# 407-io.net
KiCad netlist of a schematic drawn in Altium Designer
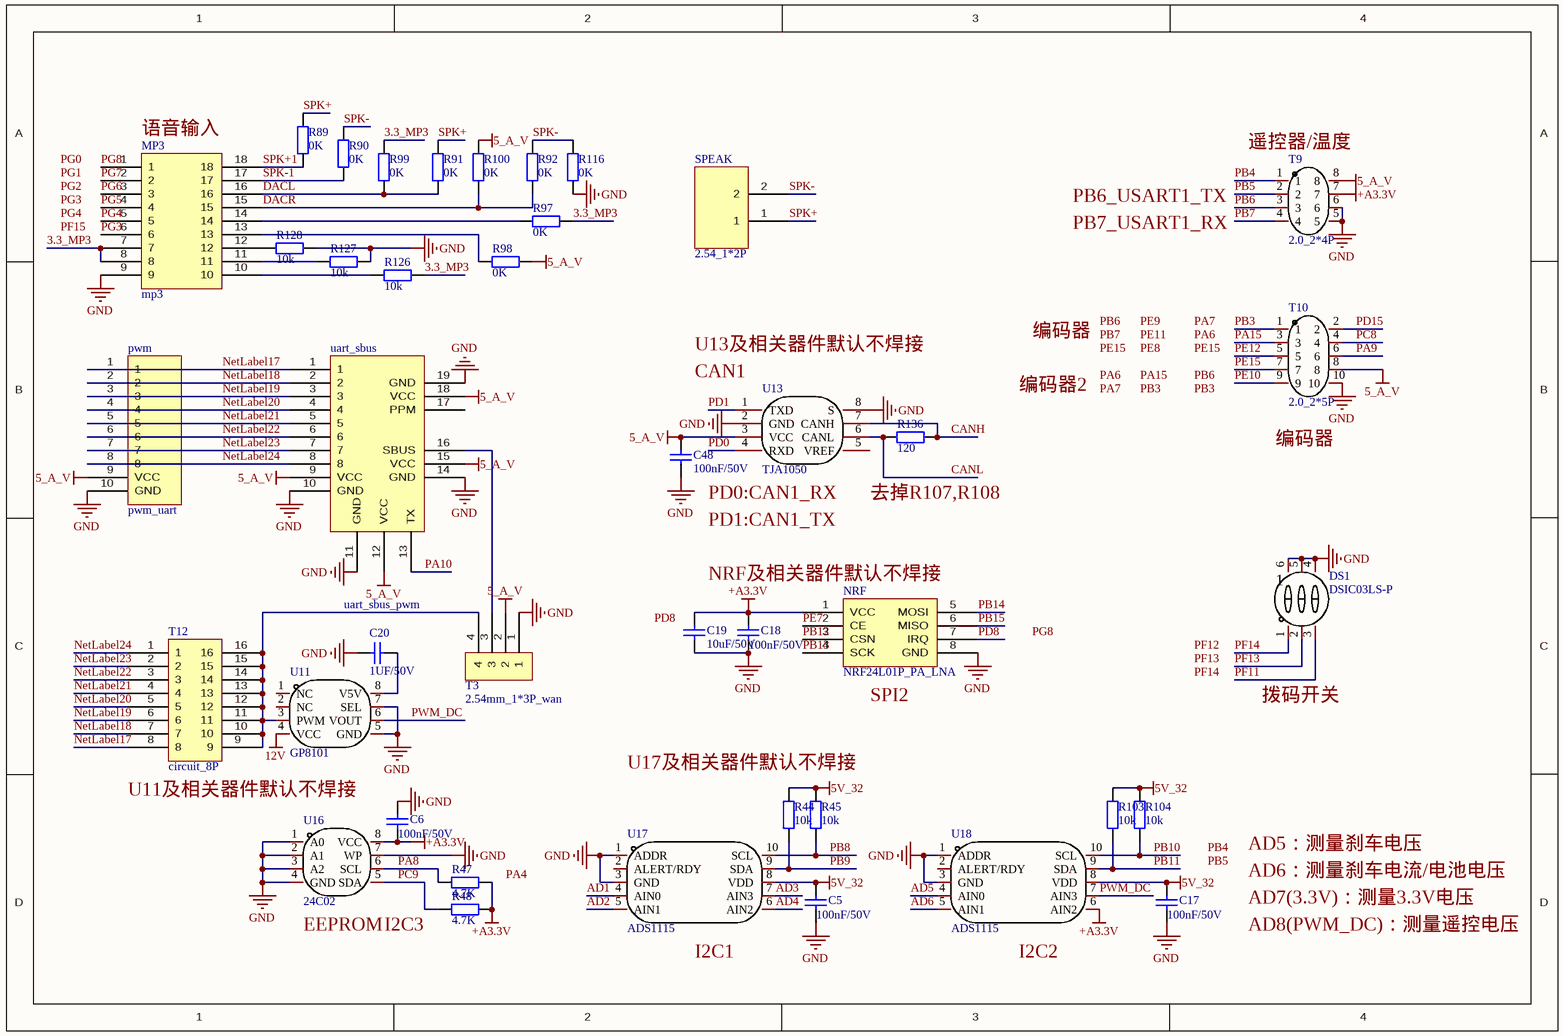
[diagram p0: 407-io.schdoc]

(export (version "E")
  (design (tool "Eeschema 10.0.6"))
  (components
    (comp (ref "C5")
      (value "100nF/50V")
      (description "Capacitor")
      (fields (field (name "PUBLISHER") "Altium Limited"))
      (libsource (lib "Miscellaneous Devices") (part "Cap"))
    )
    (comp (ref "C6")
      (value "100nF/50V")
      (description "Capacitor")
      (fields (field (name "PUBLISHER") "Altium Limited"))
      (libsource (lib "Miscellaneous Devices") (part "Cap"))
    )
    (comp (ref "C17")
      (value "100nF/50V")
      (description "Capacitor")
      (fields (field (name "PUBLISHER") "Altium Limited"))
      (libsource (lib "Miscellaneous Devices") (part "Cap"))
    )
    (comp (ref "C18")
      (value "100nF/50V")
      (description "Capacitor")
      (fields (field (name "PUBLISHER") "Altium Limited"))
      (libsource (lib "Miscellaneous Devices") (part "Cap"))
    )
    (comp (ref "C19")
      (value "10uF/50V")
      (description "Capacitor")
      (fields (field (name "PUBLISHER") "Altium Limited"))
      (libsource (lib "Miscellaneous Devices") (part "Cap"))
    )
    (comp (ref "C20")
      (value "1UF/50V")
      (description "Capacitor")
      (fields (field (name "PUBLISHER") "Altium Limited"))
      (libsource (lib "Miscellaneous Devices") (part "Cap"))
    )
    (comp (ref "C48")
      (value "100nF/50V")
      (description "Capacitor")
      (fields (field (name "PUBLISHER") "Altium Limited"))
      (libsource (lib "Miscellaneous Devices") (part "Cap"))
    )
    (comp (ref "DS1")
      (value "DSIC03LS-P")
      (footprint "DS1040-03RN")
      (libsource (lib "tianjin_2023") (part "DSIC03LS-P"))
    )
    (comp (ref "MP3") (value "mp3") (footprint "MP3") (libsource (lib "tianjin_2023") (part "mp3")))
    (comp (ref "NRF")
      (value "NRF24L01P_PA_LNA")
      (footprint "NRF24L01P_PA_LNA")
      (libsource (lib "tianjin_2023") (part "NRF24L01P_PA_LNA"))
    )
    (comp (ref "pwm")
      (value "pwm_uart")
      (footprint "pwm_uart")
      (libsource (lib "tianjin_2023") (part "pwm_uart"))
    )
    (comp (ref "R44")
      (value "10k")
      (footprint "R0603_L")
      (description "Resistor")
      (fields (field (name "PUBLISHER") "Altium Limited"))
      (libsource (lib "") (part "Res2_1"))
    )
    (comp (ref "R45")
      (value "10k")
      (footprint "R0603_L")
      (description "Resistor")
      (fields (field (name "PUBLISHER") "Altium Limited"))
      (libsource (lib "") (part "Res2_1"))
    )
    (comp (ref "R47")
      (value "4.7K")
      (description "Resistor")
      (fields (field (name "PUBLISHER") "Altium Limited"))
      (libsource (lib "") (part "Res2_2"))
    )
    (comp (ref "R48")
      (value "4.7K")
      (description "Resistor")
      (fields (field (name "PUBLISHER") "Altium Limited"))
      (libsource (lib "") (part "Res2_2"))
    )
    (comp (ref "R89")
      (value "0K")
      (footprint "R0603_L")
      (description "Resistor")
      (fields (field (name "PUBLISHER") "Altium Limited"))
      (libsource (lib "MOS motor driving module ") (part "Res2"))
    )
    (comp (ref "R90")
      (value "0K")
      (footprint "R0603_L")
      (description "Resistor")
      (fields (field (name "PUBLISHER") "Altium Limited"))
      (libsource (lib "MOS motor driving module ") (part "Res2"))
    )
    (comp (ref "R91")
      (value "0K")
      (footprint "R0603_L")
      (description "Resistor")
      (fields (field (name "PUBLISHER") "Altium Limited"))
      (libsource (lib "MOS motor driving module ") (part "Res2"))
    )
    (comp (ref "R92")
      (value "0K")
      (footprint "R0603_L")
      (description "Resistor")
      (fields (field (name "PUBLISHER") "Altium Limited"))
      (libsource (lib "MOS motor driving module ") (part "Res2"))
    )
    (comp (ref "R97")
      (value "0K")
      (footprint "R0603_L")
      (description "Resistor")
      (fields (field (name "PUBLISHER") "Altium Limited"))
      (libsource (lib "") (part "Res2_2"))
    )
    (comp (ref "R98")
      (value "0K")
      (footprint "R0603_L")
      (description "Resistor")
      (fields (field (name "PUBLISHER") "Altium Limited"))
      (libsource (lib "") (part "Res2_2"))
    )
    (comp (ref "R99")
      (value "0K")
      (footprint "R0603_L")
      (description "Resistor")
      (fields (field (name "PUBLISHER") "Altium Limited"))
      (libsource (lib "MOS motor driving module ") (part "Res2"))
    )
    (comp (ref "R100")
      (value "0K")
      (footprint "R0603_L")
      (description "Resistor")
      (fields (field (name "PUBLISHER") "Altium Limited"))
      (libsource (lib "MOS motor driving module ") (part "Res2"))
    )
    (comp (ref "R103")
      (value "10k")
      (footprint "R0603_L")
      (description "Resistor")
      (fields (field (name "PUBLISHER") "Altium Limited"))
      (libsource (lib "") (part "Res2_1"))
    )
    (comp (ref "R104")
      (value "10k")
      (footprint "R0603_L")
      (description "Resistor")
      (fields (field (name "PUBLISHER") "Altium Limited"))
      (libsource (lib "") (part "Res2_1"))
    )
    (comp (ref "R116")
      (value "0K")
      (footprint "R0603_L")
      (description "Resistor")
      (fields (field (name "PUBLISHER") "Altium Limited"))
      (libsource (lib "MOS motor driving module ") (part "Res2"))
    )
    (comp (ref "R126")
      (value "10k")
      (footprint "R0603_L")
      (description "Resistor")
      (fields (field (name "PUBLISHER") "Altium Limited"))
      (libsource (lib "") (part "Res2_2"))
    )
    (comp (ref "R127")
      (value "10k")
      (footprint "R0603_L")
      (description "Resistor")
      (fields (field (name "PUBLISHER") "Altium Limited"))
      (libsource (lib "") (part "Res2_2"))
    )
    (comp (ref "R128")
      (value "10k")
      (footprint "R0603_L")
      (description "Resistor")
      (fields (field (name "PUBLISHER") "Altium Limited"))
      (libsource (lib "") (part "Res2_2"))
    )
    (comp (ref "R136")
      (value "120")
      (description "Resistor")
      (fields (field (name "PUBLISHER") "Altium Limited"))
      (libsource (lib "") (part "Res2_2"))
    )
    (comp (ref "SPEAK")
      (value "2.54_1*2P")
      (footprint "2.54_1*2P")
      (libsource (lib "tianjin_2023") (part "2.54_1*2P"))
    )
    (comp (ref "T3") (value "2.54mm_1*3P_wan") (libsource (lib "tianjin_2023") (part "2.54mm_1*3P_wan")))
    (comp (ref "T9")
      (value "2.0_2*4P")
      (footprint "2.0_2*4P")
      (libsource (lib "tianjin_2023") (part "2.0_2*4P"))
    )
    (comp (ref "T10")
      (value "2.0_2*5P")
      (footprint "2.0_2*5P")
      (libsource (lib "tianjin_2023") (part "2.0_2*5P"))
    )
    (comp (ref "T12")
      (value "circuit_8P")
      (footprint "circuit_8P")
      (libsource (lib "tianjin_2023") (part "circuit_8P"))
    )
    (comp (ref "U11") (value "GP8101") (footprint "GP8101") (libsource (lib "tianjin_2023") (part "GP8101")))
    (comp (ref "U13")
      (value "TJA1050")
      (footprint "TJA1050")
      (libsource (lib "tianjin_2023") (part "TJA1050"))
    )
    (comp (ref "U16") (value "24C02") (footprint "24C02") (libsource (lib "tianjin_2023") (part "24C02")))
    (comp (ref "U17")
      (value "ADS1115")
      (footprint "ADS1115")
      (libsource (lib "tianjin_2023") (part "ADS1115"))
    )
    (comp (ref "U18")
      (value "ADS1115")
      (footprint "ADS1115")
      (libsource (lib "tianjin_2023") (part "ADS1115"))
    )
    (comp (ref "uart_sbus")
      (value "uart_sbus_pwm")
      (footprint "uart_sbus_pwm")
      (libsource (lib "tianjin_2023") (part "uart_sbus_pwm"))
    )
  )
  (nets
    (net (code "1") (name "+A3.3V") (class "Default")
      (node (ref "C18") (pin "1") (pinfunction "1_1") (pintype "passive"))
      (node (ref "C19") (pin "1") (pinfunction "1_1") (pintype "passive"))
      (node (ref "C6") (pin "2") (pinfunction "2_2") (pintype "passive"))
      (node (ref "NRF") (pin "1") (pinfunction "VCC_1") (pintype "passive"))
      (node (ref "R47") (pin "2") (pinfunction "2_2") (pintype "passive"))
      (node (ref "R48") (pin "2") (pinfunction "2_2") (pintype "passive"))
      (node (ref "T9") (pin "7") (pinfunction "7_7") (pintype "passive"))
      (node (ref "U16") (pin "8") (pinfunction "VCC_8") (pintype "passive"))
      (node (ref "U18") (pin "6") (pinfunction "AIN2_6") (pintype "passive"))
    )
    (net (code "2") (name "/3.3_MP3") (class "Default")
      (node (ref "MP3") (pin "7") (pinfunction "7_7") (pintype "passive"))
      (node (ref "MP3") (pin "8") (pinfunction "8_8") (pintype "passive"))
      (node (ref "R126") (pin "2") (pinfunction "2_2") (pintype "passive"))
      (node (ref "R97") (pin "2") (pinfunction "2_2") (pintype "passive"))
      (node (ref "R99") (pin "2") (pinfunction "2_2") (pintype "passive"))
    )
    (net (code "3") (name "/AD1") (class "Default")
      (node (ref "U17") (pin "4") (pinfunction "AIN0_4") (pintype "passive"))
    )
    (net (code "4") (name "/AD2") (class "Default")
      (node (ref "U17") (pin "5") (pinfunction "AIN1_5") (pintype "passive"))
    )
    (net (code "5") (name "/AD3") (class "Default")
      (node (ref "U17") (pin "7") (pinfunction "AIN3_7") (pintype "passive"))
    )
    (net (code "6") (name "/AD4") (class "Default")
      (node (ref "U17") (pin "6") (pinfunction "AIN2_6") (pintype "passive"))
    )
    (net (code "7") (name "/AD5") (class "Default")
      (node (ref "U18") (pin "4") (pinfunction "AIN0_4") (pintype "passive"))
    )
    (net (code "8") (name "/AD6") (class "Default")
      (node (ref "U18") (pin "5") (pinfunction "AIN1_5") (pintype "passive"))
    )
    (net (code "9") (name "/CANH") (class "Default")
      (node (ref "R136") (pin "2") (pinfunction "2_2") (pintype "passive"))
      (node (ref "U13") (pin "7") (pinfunction "CANH_7") (pintype "passive"))
    )
    (net (code "10") (name "/CANL") (class "Default")
      (node (ref "R136") (pin "1") (pinfunction "1_1") (pintype "passive"))
      (node (ref "U13") (pin "6") (pinfunction "CANL_6") (pintype "passive"))
    )
    (net (code "11") (name "/DACL") (class "Default")
      (node (ref "MP3") (pin "16") (pinfunction "16_16") (pintype "passive"))
      (node (ref "R91") (pin "1") (pinfunction "1_1") (pintype "passive"))
      (node (ref "R99") (pin "1") (pinfunction "1_1") (pintype "passive"))
    )
    (net (code "12") (name "/DACR") (class "Default")
      (node (ref "MP3") (pin "15") (pinfunction "15_15") (pintype "passive"))
      (node (ref "R100") (pin "1") (pinfunction "1_1") (pintype "passive"))
      (node (ref "R92") (pin "1") (pinfunction "1_1") (pintype "passive"))
    )
    (net (code "13") (name "/NetLabel17") (class "Default")
      (node (ref "T12") (pin "8") (pinfunction "8_8") (pintype "passive"))
      (node (ref "pwm") (pin "1") (pinfunction "1_1") (pintype "passive"))
      (node (ref "uart_sbus") (pin "1") (pinfunction "1_1") (pintype "passive"))
    )
    (net (code "14") (name "/NetLabel18") (class "Default")
      (node (ref "T12") (pin "7") (pinfunction "7_7") (pintype "passive"))
      (node (ref "pwm") (pin "2") (pinfunction "2_2") (pintype "passive"))
      (node (ref "uart_sbus") (pin "2") (pinfunction "2_2") (pintype "passive"))
    )
    (net (code "15") (name "/NetLabel19") (class "Default")
      (node (ref "T12") (pin "6") (pinfunction "6_6") (pintype "passive"))
      (node (ref "pwm") (pin "3") (pinfunction "3_3") (pintype "passive"))
      (node (ref "uart_sbus") (pin "3") (pinfunction "3_3") (pintype "passive"))
    )
    (net (code "16") (name "/NetLabel20") (class "Default")
      (node (ref "T12") (pin "5") (pinfunction "5_5") (pintype "passive"))
      (node (ref "pwm") (pin "4") (pinfunction "4_4") (pintype "passive"))
      (node (ref "uart_sbus") (pin "4") (pinfunction "4_4") (pintype "passive"))
    )
    (net (code "17") (name "/NetLabel21") (class "Default")
      (node (ref "T12") (pin "4") (pinfunction "4_4") (pintype "passive"))
      (node (ref "pwm") (pin "5") (pinfunction "5_5") (pintype "passive"))
      (node (ref "uart_sbus") (pin "5") (pinfunction "5_5") (pintype "passive"))
    )
    (net (code "18") (name "/NetLabel22") (class "Default")
      (node (ref "T12") (pin "3") (pinfunction "3_3") (pintype "passive"))
      (node (ref "pwm") (pin "6") (pinfunction "6_6") (pintype "passive"))
      (node (ref "uart_sbus") (pin "6") (pinfunction "6_6") (pintype "passive"))
    )
    (net (code "19") (name "/NetLabel23") (class "Default")
      (node (ref "T12") (pin "2") (pinfunction "2_2") (pintype "passive"))
      (node (ref "pwm") (pin "7") (pinfunction "7_7") (pintype "passive"))
      (node (ref "uart_sbus") (pin "7") (pinfunction "7_7") (pintype "passive"))
    )
    (net (code "20") (name "/NetLabel24") (class "Default")
      (node (ref "T12") (pin "1") (pinfunction "1_1") (pintype "passive"))
      (node (ref "pwm") (pin "8") (pinfunction "8_8") (pintype "passive"))
      (node (ref "uart_sbus") (pin "8") (pinfunction "8_8") (pintype "passive"))
    )
    (net (code "24") (name "/PA8") (class "Default")
      (node (ref "R47") (pin "1") (pinfunction "1_1") (pintype "passive"))
      (node (ref "U16") (pin "6") (pinfunction "SCL_6") (pintype "passive"))
    )
    (net (code "25") (name "/PA9") (class "Default")
      (node (ref "T10") (pin "6") (pinfunction "6_6") (pintype "passive"))
    )
    (net (code "26") (name "/PA10") (class "Default")
      (node (ref "uart_sbus") (pin "13") (pinfunction "TX_13") (pintype "passive"))
    )
    (net (code "27") (name "/PA15") (class "Default")
      (node (ref "T10") (pin "3") (pinfunction "3_3") (pintype "passive"))
    )
    (net (code "28") (name "/PB3") (class "Default")
      (node (ref "T10") (pin "1") (pinfunction "1_1") (pintype "passive"))
    )
    (net (code "29") (name "/PB4") (class "Default")
      (node (ref "T9") (pin "1") (pinfunction "1_1") (pintype "passive"))
    )
    (net (code "30") (name "/PB5") (class "Default")
      (node (ref "T9") (pin "2") (pinfunction "2_2") (pintype "passive"))
    )
    (net (code "31") (name "/PB6") (class "Default")
      (node (ref "T9") (pin "3") (pinfunction "3_3") (pintype "passive"))
    )
    (net (code "32") (name "/PB7") (class "Default")
      (node (ref "T9") (pin "4") (pinfunction "4_4") (pintype "passive"))
    )
    (net (code "33") (name "/PB8") (class "Default")
      (node (ref "R45") (pin "2") (pinfunction "2_2") (pintype "passive"))
      (node (ref "U17") (pin "10") (pinfunction "SCL_10") (pintype "passive"))
    )
    (net (code "34") (name "/PB9") (class "Default")
      (node (ref "R44") (pin "2") (pinfunction "2_2") (pintype "passive"))
      (node (ref "U17") (pin "9") (pinfunction "SDA_9") (pintype "passive"))
    )
    (net (code "35") (name "/PB10") (class "Default")
      (node (ref "R104") (pin "2") (pinfunction "2_2") (pintype "passive"))
      (node (ref "U18") (pin "10") (pinfunction "SCL_10") (pintype "passive"))
    )
    (net (code "36") (name "/PB11") (class "Default")
      (node (ref "R103") (pin "2") (pinfunction "2_2") (pintype "passive"))
      (node (ref "U18") (pin "9") (pinfunction "SDA_9") (pintype "passive"))
    )
    (net (code "37") (name "/PB12") (class "Default")
      (node (ref "NRF") (pin "3") (pinfunction "CSN_3") (pintype "passive"))
    )
    (net (code "38") (name "/PB13") (class "Default")
      (node (ref "NRF") (pin "4") (pinfunction "SCK_4") (pintype "passive"))
    )
    (net (code "39") (name "/PB14") (class "Default")
      (node (ref "NRF") (pin "5") (pinfunction "MOSI_5") (pintype "passive"))
    )
    (net (code "40") (name "/PB15") (class "Default")
      (node (ref "NRF") (pin "6") (pinfunction "MISO_6") (pintype "passive"))
    )
    (net (code "41") (name "/PC8") (class "Default")
      (node (ref "T10") (pin "4") (pinfunction "4_4") (pintype "passive"))
    )
    (net (code "42") (name "/PC9") (class "Default")
      (node (ref "R48") (pin "1") (pinfunction "1_1") (pintype "passive"))
      (node (ref "U16") (pin "5") (pinfunction "SDA_5") (pintype "passive"))
    )
    (net (code "43") (name "/PD0") (class "Default")
      (node (ref "U13") (pin "4") (pinfunction "RXD_4") (pintype "passive"))
    )
    (net (code "44") (name "/PD1") (class "Default")
      (node (ref "U13") (pin "1") (pinfunction "TXD_1") (pintype "passive"))
    )
    (net (code "45") (name "/PD8") (class "Default")
      (node (ref "NRF") (pin "7") (pinfunction "IRQ_7") (pintype "passive"))
    )
    (net (code "46") (name "/PD15") (class "Default")
      (node (ref "T10") (pin "2") (pinfunction "2_2") (pintype "passive"))
    )
    (net (code "47") (name "/PE7") (class "Default")
      (node (ref "NRF") (pin "2") (pinfunction "CE_2") (pintype "passive"))
    )
    (net (code "50") (name "/PE10") (class "Default")
      (node (ref "T10") (pin "9") (pinfunction "9_9") (pintype "passive"))
    )
    (net (code "52") (name "/PE12") (class "Default")
      (node (ref "T10") (pin "5") (pinfunction "5_5") (pintype "passive"))
    )
    (net (code "53") (name "/PE15") (class "Default")
      (node (ref "T10") (pin "7") (pinfunction "7_7") (pintype "passive"))
    )
    (net (code "54") (name "/PF11") (class "Default")
      (node (ref "DS1") (pin "3") (pinfunction "PIN3_3") (pintype "passive"))
    )
    (net (code "56") (name "/PF13") (class "Default")
      (node (ref "DS1") (pin "2") (pinfunction "PIN2_2") (pintype "passive"))
    )
    (net (code "57") (name "/PF14") (class "Default")
      (node (ref "DS1") (pin "1") (pinfunction "PIN1_1") (pintype "passive"))
    )
    (net (code "62") (name "/PG3") (class "Default")
      (node (ref "MP3") (pin "6") (pinfunction "6_6") (pintype "passive"))
    )
    (net (code "63") (name "/PG4") (class "Default")
      (node (ref "MP3") (pin "5") (pinfunction "5_5") (pintype "passive"))
    )
    (net (code "64") (name "/PG5") (class "Default")
      (node (ref "MP3") (pin "4") (pinfunction "4_4") (pintype "passive"))
    )
    (net (code "65") (name "/PG6") (class "Default")
      (node (ref "MP3") (pin "3") (pinfunction "3_3") (pintype "passive"))
    )
    (net (code "66") (name "/PG7") (class "Default")
      (node (ref "MP3") (pin "2") (pinfunction "2_2") (pintype "passive"))
    )
    (net (code "67") (name "/PG8") (class "Default")
      (node (ref "MP3") (pin "1") (pinfunction "1_1") (pintype "passive"))
    )
    (net (code "68") (name "/PWM_DC") (class "Default")
      (node (ref "U11") (pin "6") (pinfunction "VOUT_6") (pintype "passive"))
      (node (ref "U18") (pin "7") (pinfunction "AIN3_7") (pintype "passive"))
    )
    (net (code "69") (name "/SPK+") (class "Default")
      (node (ref "R89") (pin "2") (pinfunction "2_2") (pintype "passive"))
      (node (ref "R91") (pin "2") (pinfunction "2_2") (pintype "passive"))
      (node (ref "SPEAK") (pin "1") (pinfunction "1_1") (pintype "passive"))
    )
    (net (code "70") (name "/SPK+1") (class "Default")
      (node (ref "MP3") (pin "18") (pinfunction "18_18") (pintype "passive"))
      (node (ref "R89") (pin "1") (pinfunction "1_1") (pintype "passive"))
    )
    (net (code "71") (name "/SPK-") (class "Default")
      (node (ref "R116") (pin "2") (pinfunction "2_2") (pintype "passive"))
      (node (ref "R90") (pin "2") (pinfunction "2_2") (pintype "passive"))
      (node (ref "R92") (pin "2") (pinfunction "2_2") (pintype "passive"))
      (node (ref "SPEAK") (pin "2") (pinfunction "2_2") (pintype "passive"))
    )
    (net (code "72") (name "/SPK-1") (class "Default")
      (node (ref "MP3") (pin "17") (pinfunction "17_17") (pintype "passive"))
      (node (ref "R90") (pin "1") (pinfunction "1_1") (pintype "passive"))
    )
    (net (code "73") (name "5V_32") (class "Default")
      (node (ref "C17") (pin "1") (pinfunction "1_1") (pintype "passive"))
      (node (ref "C5") (pin "1") (pinfunction "1_1") (pintype "passive"))
      (node (ref "R103") (pin "1") (pinfunction "1_1") (pintype "passive"))
      (node (ref "R104") (pin "1") (pinfunction "1_1") (pintype "passive"))
      (node (ref "R44") (pin "1") (pinfunction "1_1") (pintype "passive"))
      (node (ref "R45") (pin "1") (pinfunction "1_1") (pintype "passive"))
      (node (ref "U17") (pin "8") (pinfunction "VDD_8") (pintype "passive"))
      (node (ref "U18") (pin "8") (pinfunction "VDD_8") (pintype "passive"))
    )
    (net (code "74") (name "5_A_V") (class "Default")
      (node (ref "C48") (pin "2") (pinfunction "2_2") (pintype "passive"))
      (node (ref "R100") (pin "2") (pinfunction "2_2") (pintype "passive"))
      (node (ref "R98") (pin "2") (pinfunction "2_2") (pintype "passive"))
      (node (ref "T10") (pin "8") (pinfunction "8_8") (pintype "passive"))
      (node (ref "T3") (pin "2") (pinfunction "2_2") (pintype "passive"))
      (node (ref "T9") (pin "8") (pinfunction "8_8") (pintype "passive"))
      (node (ref "U13") (pin "3") (pinfunction "VCC_3") (pintype "passive"))
      (node (ref "pwm") (pin "9") (pinfunction "VCC_9") (pintype "passive"))
      (node (ref "uart_sbus") (pin "12") (pinfunction "VCC_12") (pintype "passive"))
      (node (ref "uart_sbus") (pin "15") (pinfunction "VCC_15") (pintype "passive"))
      (node (ref "uart_sbus") (pin "18") (pinfunction "VCC_18") (pintype "passive"))
      (node (ref "uart_sbus") (pin "9") (pinfunction "VCC_9") (pintype "passive"))
    )
    (net (code "75") (name "12V") (class "Default")
      (node (ref "U11") (pin "4") (pinfunction "VCC_4") (pintype "passive"))
    )
    (net (code "76") (name "GND") (class "Default")
      (node (ref "C17") (pin "2") (pinfunction "2_2") (pintype "passive"))
      (node (ref "C18") (pin "2") (pinfunction "2_2") (pintype "passive"))
      (node (ref "C19") (pin "2") (pinfunction "2_2") (pintype "passive"))
      (node (ref "C20") (pin "2") (pinfunction "2_2") (pintype "passive"))
      (node (ref "C48") (pin "1") (pinfunction "1_1") (pintype "passive"))
      (node (ref "C5") (pin "2") (pinfunction "2_2") (pintype "passive"))
      (node (ref "C6") (pin "1") (pinfunction "1_1") (pintype "passive"))
      (node (ref "DS1") (pin "4") (pinfunction "PIN4_4") (pintype "passive"))
      (node (ref "DS1") (pin "5") (pinfunction "PIN5_5") (pintype "passive"))
      (node (ref "DS1") (pin "6") (pinfunction "PIN6_6") (pintype "passive"))
      (node (ref "MP3") (pin "9") (pinfunction "9_9") (pintype "passive"))
      (node (ref "NRF") (pin "8") (pinfunction "GND_8") (pintype "passive"))
      (node (ref "R116") (pin "1") (pinfunction "1_1") (pintype "passive"))
      (node (ref "R127") (pin "2") (pinfunction "2_2") (pintype "passive"))
      (node (ref "R128") (pin "2") (pinfunction "2_2") (pintype "passive"))
      (node (ref "T10") (pin "10") (pinfunction "10_10") (pintype "passive"))
      (node (ref "T3") (pin "1") (pinfunction "1_1") (pintype "passive"))
      (node (ref "T9") (pin "5") (pinfunction "5_5") (pintype "passive"))
      (node (ref "T9") (pin "6") (pinfunction "6_6") (pintype "passive"))
      (node (ref "U11") (pin "5") (pinfunction "GND_5") (pintype "passive"))
      (node (ref "U11") (pin "7") (pinfunction "SEL_7") (pintype "passive"))
      (node (ref "U13") (pin "2") (pinfunction "GND_2") (pintype "passive"))
      (node (ref "U13") (pin "8") (pinfunction "S_8") (pintype "passive"))
      (node (ref "U16") (pin "1") (pinfunction "A0_1") (pintype "passive"))
      (node (ref "U16") (pin "2") (pinfunction "A1_2") (pintype "passive"))
      (node (ref "U16") (pin "3") (pinfunction "A2_3") (pintype "passive"))
      (node (ref "U16") (pin "4") (pinfunction "GND_4") (pintype "passive"))
      (node (ref "U16") (pin "7") (pinfunction "WP_7") (pintype "passive"))
      (node (ref "U17") (pin "1") (pinfunction "ADDR_1") (pintype "passive"))
      (node (ref "U17") (pin "3") (pinfunction "GND_3") (pintype "passive"))
      (node (ref "U18") (pin "1") (pinfunction "ADDR_1") (pintype "passive"))
      (node (ref "U18") (pin "3") (pinfunction "GND_3") (pintype "passive"))
      (node (ref "pwm") (pin "10") (pinfunction "GND_10") (pintype "passive"))
      (node (ref "uart_sbus") (pin "10") (pinfunction "GND_10") (pintype "passive"))
      (node (ref "uart_sbus") (pin "11") (pinfunction "GND_11") (pintype "passive"))
      (node (ref "uart_sbus") (pin "14") (pinfunction "GND_14") (pintype "passive"))
      (node (ref "uart_sbus") (pin "19") (pinfunction "GND_19") (pintype "passive"))
    )
    (net (code "77") (name "Net-(MP3-Pad10)") (class "Default")
      (node (ref "MP3") (pin "10") (pinfunction "10_10") (pintype "passive"))
      (node (ref "R126") (pin "1") (pinfunction "1_1") (pintype "passive"))
    )
    (net (code "78") (name "Net-(MP3-Pad11)") (class "Default")
      (node (ref "MP3") (pin "11") (pinfunction "11_11") (pintype "passive"))
      (node (ref "R127") (pin "1") (pinfunction "1_1") (pintype "passive"))
    )
    (net (code "79") (name "Net-(MP3-Pad12)") (class "Default")
      (node (ref "MP3") (pin "12") (pinfunction "12_12") (pintype "passive"))
      (node (ref "R128") (pin "1") (pinfunction "1_1") (pintype "passive"))
    )
    (net (code "80") (name "Net-(MP3-Pad13)") (class "Default")
      (node (ref "MP3") (pin "13") (pinfunction "13_13") (pintype "passive"))
      (node (ref "R98") (pin "1") (pinfunction "1_1") (pintype "passive"))
    )
    (net (code "81") (name "Net-(MP3-Pad14)") (class "Default")
      (node (ref "MP3") (pin "14") (pinfunction "14_14") (pintype "passive"))
      (node (ref "R97") (pin "1") (pinfunction "1_1") (pintype "passive"))
    )
    (net (code "82") (name "Net-(U11-PWM)") (class "Default")
      (node (ref "T12") (pin "10") (pinfunction "10_10") (pintype "passive"))
      (node (ref "T12") (pin "11") (pinfunction "11_11") (pintype "passive"))
      (node (ref "T12") (pin "12") (pinfunction "12_12") (pintype "passive"))
      (node (ref "T12") (pin "13") (pinfunction "13_13") (pintype "passive"))
      (node (ref "T12") (pin "14") (pinfunction "14_14") (pintype "passive"))
      (node (ref "T12") (pin "15") (pinfunction "15_15") (pintype "passive"))
      (node (ref "T12") (pin "16") (pinfunction "16_16") (pintype "passive"))
      (node (ref "T12") (pin "9") (pinfunction "9_9") (pintype "passive"))
      (node (ref "T3") (pin "4") (pinfunction "4_4") (pintype "passive"))
      (node (ref "U11") (pin "3") (pinfunction "PWM_3") (pintype "passive"))
    )
    (net (code "83") (name "Net-(U11-V5V)") (class "Default")
      (node (ref "C20") (pin "1") (pinfunction "1_1") (pintype "passive"))
      (node (ref "U11") (pin "8") (pinfunction "V5V_8") (pintype "passive"))
    )
    (net (code "84") (name "Net-(uart_sbus-SBUS)") (class "Default")
      (node (ref "T3") (pin "3") (pinfunction "3_3") (pintype "passive"))
      (node (ref "uart_sbus") (pin "16") (pinfunction "SBUS_16") (pintype "passive"))
    )
    (net (code "85") (name "unconnected-(U11-NC-Pad1)") (class "Default")
      (node (ref "U11") (pin "1") (pinfunction "NC_1") (pintype "passive"))
    )
    (net (code "86") (name "unconnected-(U11-NC-Pad2)") (class "Default")
      (node (ref "U11") (pin "2") (pinfunction "NC_2") (pintype "passive"))
    )
    (net (code "87") (name "unconnected-(U13-VREF-Pad5)") (class "Default")
      (node (ref "U13") (pin "5") (pinfunction "VREF_5") (pintype "passive"))
    )
    (net (code "88") (name "unconnected-(U17-ALERT{slash}RDY-Pad2)") (class "Default")
      (node (ref "U17") (pin "2") (pinfunction "ALERT/RDY_2") (pintype "passive"))
    )
    (net (code "89") (name "unconnected-(U18-ALERT{slash}RDY-Pad2)") (class "Default")
      (node (ref "U18") (pin "2") (pinfunction "ALERT/RDY_2") (pintype "passive"))
    )
    (net (code "90") (name "unconnected-(uart_sbus-PPM-Pad17)") (class "Default")
      (node (ref "uart_sbus") (pin "17") (pinfunction "PPM_17") (pintype "passive"))
    )
  )
)
